# BatteryPower.net
KiCad netlist of a schematic drawn in Altium Designer
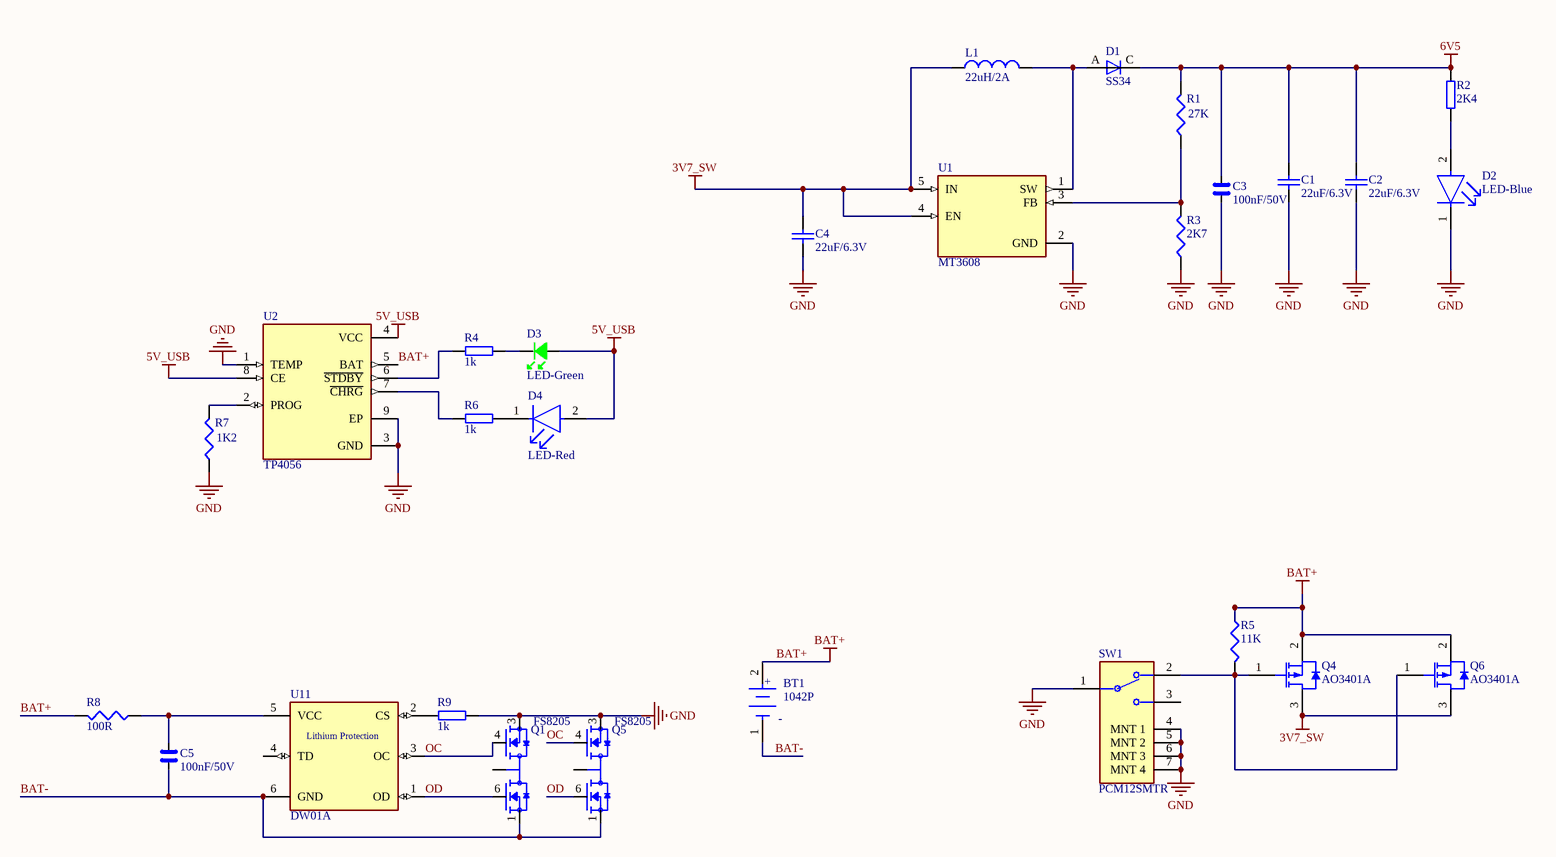
[diagram p0: BatteryPower.SchDoc]

(export (version "E")
  (design (tool "Eeschema 10.0.6"))
  (components
    (comp (ref "BT1")
      (value "1042P")
      (footprint "FP-1042P-MFG")
      (description "BATTERY HOLDER 18650 SMD TAB")
      (fields (field (name "LCSCPARTNO") "C2988620"))
      (libsource (lib "Altium Content Vault") (part "60d3b5b901a8747834971d0eb8cf3fd"))
    )
    (comp (ref "C1")
      (value "22uF/6.3V")
      (footprint "1608[0603]")
      (description "Capacitor")
      (fields (field (name "LCSCPARTNO") "C59461"))
      (libsource (lib "Miscellaneous Devices") (part "Cap"))
    )
    (comp (ref "C2")
      (value "22uF/6.3V")
      (footprint "1608[0603]")
      (description "Capacitor")
      (fields (field (name "LCSCPARTNO") "C59461"))
      (libsource (lib "Miscellaneous Devices") (part "Cap"))
    )
    (comp (ref "C3")
      (value "100nF/50V")
      (footprint "1608[0603]")
      (description "Cap Ceramic 0.1uF 50V X7R 20% SMD 0603 125C Paper T/R")
      (fields (field (name "LCSCPARTNO") "C14663"))
      (libsource (lib "Sch") (part "C"))
    )
    (comp (ref "C4")
      (value "22uF/6.3V")
      (footprint "1608[0603]")
      (description "Capacitor")
      (fields (field (name "LCSCPARTNO") "C59461"))
      (libsource (lib "Miscellaneous Devices") (part "Cap"))
    )
    (comp (ref "C5")
      (value "100nF/50V")
      (footprint "1608[0603]")
      (description "Cap Ceramic 0.1uF 50V X7R 20% SMD 0603 125C Paper T/R")
      (fields (field (name "LCSCPARTNO") "C14663"))
      (libsource (lib "Sch") (part "C"))
    )
    (comp (ref "D1")
      (value "SS34")
      (footprint "SMA:DIOM449X264X300L114X135N")
      (description "0.5mA@40V 40V Single 3A 0.55V@3A SMA(DO-214AC) Schottky")
      (fields (field (name "LCSCPARTNO") "C8678"))
      (libsource (lib "SMA") (part "EGF1B"))
    )
    (comp (ref "D2")
      (value "LED-Blue")
      (footprint "FP-LTST-C193TBKT-5A-MFG")
      (description "LED BLUE CLEAR CHIP SMD")
      (fields (field (name "LCSCPARTNO") "C72041"))
      (libsource (lib "Altium Content Vault") (part "8706943c75ba83719d021d2fdc84c58"))
    )
    (comp (ref "D3")
      (value "LED-Green")
      (footprint "LED0603G")
      (description "LED GREEN CLEAR CHIP SMD")
      (fields (field (name "LCSCPARTNO") "C72043"))
      (libsource (lib "Sch") (part "LED-G"))
    )
    (comp (ref "D4")
      (value "LED-Red")
      (footprint "FP-LTST-C193KRKT-5A-MFG")
      (description "LED RED CLEAR CHIP SMD")
      (fields (field (name "LCSCPARTNO") "C2286"))
      (libsource (lib "Altium Content Vault") (part "8706943c75ba83719d021d2fdc84c58"))
    )
    (comp (ref "L1")
      (value "22uH/2A")
      (footprint "INDM7166X18N")
      (description "Inductor")
      (fields (field (name "LCSCPARTNO") "C705336"))
      (libsource (lib "Miscellaneous Devices") (part "Inductor"))
    )
    (comp (ref "Q1")
      (value "FS8205")
      (footprint "SOT95P280X145-6N:SOT95P280X145-6N")
      (description "Dual N-Channel Enhancement Mode Power MOSFET")
      (fields (field (name "MF") "Fortune Semiconductor") (field (name "LCSCPARTNO") "C2830320"))
      (libsource (lib "FS8205") (part "FS8205"))
    )
    (comp (ref "Q4")
      (value "AO3401A")
      (footprint "AO-SOT-23-3L_V")
      (description "P-Channel MOSFET, 30 V, 4 A, -55 to 150 degC, 3-Pin SOT-23-3L, RoHS, Tape and Reel")
      (fields (field (name "LCSCPARTNO") "C15127"))
      (libsource (lib "Altium Content Vault") (part "PEMOS-GSD-3"))
    )
    (comp (ref "Q5")
      (value "FS8205")
      (footprint "SOT95P280X145-6N:SOT95P280X145-6N")
      (description "Dual N-Channel Enhancement Mode Power MOSFET")
      (fields (field (name "MF") "Fortune Semiconductor") (field (name "LCSCPARTNO") "C2830320"))
      (libsource (lib "FS8205") (part "FS8205"))
    )
    (comp (ref "Q6")
      (value "AO3401A")
      (footprint "AO-SOT-23-3L_V")
      (description "P-Channel MOSFET, 30 V, 4 A, -55 to 150 degC, 3-Pin SOT-23-3L, RoHS, Tape and Reel")
      (fields (field (name "LCSCPARTNO") "C15127"))
      (libsource (lib "Altium Content Vault") (part "PEMOS-GSD-3"))
    )
    (comp (ref "R1")
      (value "27K")
      (footprint "J1-0603")
      (description "Resistor")
      (fields (field (name "LCSCPARTNO") "C22967"))
      (libsource (lib "Miscellaneous Devices") (part "Res3"))
    )
    (comp (ref "R2")
      (value "2K4")
      (footprint "1608[0603]")
      (description "Res General Purpose Thick Film 0603 1% 1/10W ±100ppm/°C Molded SMD Paper T/R")
      (fields (field (name "LCSCPARTNO") "C22940"))
      (libsource (lib "Sch") (part "R"))
    )
    (comp (ref "R3")
      (value "2K7")
      (footprint "J1-0603")
      (description "Resistor")
      (fields (field (name "LCSCPARTNO") "C13167"))
      (libsource (lib "Miscellaneous Devices") (part "Res3"))
    )
    (comp (ref "R4")
      (value "1k")
      (footprint "1608[0603]")
      (description "Res General Purpose Thick Film 0603 1% 1/10W ±100ppm/°C Molded SMD Paper T/R")
      (fields (field (name "LCSCPARTNO") "C21190"))
      (libsource (lib "Sch") (part "R"))
    )
    (comp (ref "R5")
      (value "11K")
      (footprint "J1-0603")
      (description "Resistor")
      (fields (field (name "LCSCPARTNO") "C25950"))
      (libsource (lib "Miscellaneous Devices") (part "Res3"))
    )
    (comp (ref "R6")
      (value "1k")
      (footprint "1608[0603]")
      (description "Res General Purpose Thick Film 0603 1% 1/10W ±100ppm/°C Molded SMD Paper T/R")
      (fields (field (name "LCSCPARTNO") "C21190"))
      (libsource (lib "Sch") (part "R"))
    )
    (comp (ref "R7")
      (value "1K2")
      (footprint "J1-0603")
      (description "Resistor")
      (libsource (lib "Miscellaneous Devices") (part "Res3"))
    )
    (comp (ref "R8")
      (value "100R")
      (footprint "J1-0603")
      (description "Resistor")
      (libsource (lib "Miscellaneous Devices") (part "Res3"))
    )
    (comp (ref "R9")
      (value "1k")
      (footprint "1608[0603]")
      (description "Res General Purpose Thick Film 0603 1% 1/10W ±100ppm/°C Molded SMD Paper T/R")
      (fields (field (name "LCSCPARTNO") "C21190"))
      (libsource (lib "Sch") (part "R"))
    )
    (comp (ref "SW1")
      (value "PCM12SMTR")
      (footprint "FP-PCM12SMTR-MFG")
      (description "SWITCH SLIDE SPDT 300MA 6V")
      (fields (field (name "LCSCPARTNO") "C109335"))
      (libsource (lib "Altium Content Vault") (part "1a3f67d7e2b5469b171eeab59ffb4d2"))
    )
    (comp (ref "U1")
      (value "MT3608")
      (footprint "SOT95P280X145-6N:SOT95P280X145-6N")
      (description "High Efficiency 1.2MHz 2A Step Up Converter")
      (fields (field (name "LCSCPARTNO") "C84817"))
      (libsource (lib "MT3608") (part "MT3608"))
    )
    (comp (ref "U2")
      (value "TP4056")
      (footprint "SOP127P600X175-9N:SOP127P600X175-9N")
      (description "Complete single cell Li-Ion battery with a constant current / constant voltage linear charger")
      (fields (field (name "LCSCPARTNO") "C16581"))
      (libsource (lib "TP4056") (part "TP4056"))
    )
    (comp (ref "U11")
      (value "DW01A")
      (footprint "DW01A:SOT23-6")
      (description "SOT-23-6L Battery Management ICs ROHS")
      (fields (field (name "LCSCPARTNO") "C351410"))
      (libsource (lib "DW01A") (part "DW01A"))
    )
  )
  (nets
    (net (code "1") (name "/BAT-") (class "Default")
      (node (ref "BT1") (pin "1") (pinfunction "C_1") (pintype "passive"))
      (node (ref "C5") (pin "2") (pinfunction "2_2") (pintype "passive"))
      (node (ref "Q1") (pin "1") (pinfunction "S1_1") (pintype "passive"))
      (node (ref "Q5") (pin "1") (pinfunction "S1_1") (pintype "passive"))
      (node (ref "U11") (pin "6") (pinfunction "GND_6") (pintype "power_in"))
    )
    (net (code "2") (name "/OC") (class "Default")
      (node (ref "Q1") (pin "4") (pinfunction "G2_4") (pintype "passive"))
      (node (ref "Q5") (pin "4") (pinfunction "G2_4") (pintype "passive"))
      (node (ref "U11") (pin "3") (pinfunction "OC_3") (pintype "bidirectional"))
    )
    (net (code "3") (name "/OD") (class "Default")
      (node (ref "Q1") (pin "6") (pinfunction "G1_6") (pintype "passive"))
      (node (ref "Q5") (pin "6") (pinfunction "G1_6") (pintype "passive"))
      (node (ref "U11") (pin "1") (pinfunction "OD_1") (pintype "bidirectional"))
    )
    (net (code "4") (name "3V7_SW") (class "Default")
      (node (ref "C4") (pin "2") (pinfunction "2_2") (pintype "passive"))
      (node (ref "L1") (pin "1") (pinfunction "1_1") (pintype "passive"))
      (node (ref "Q4") (pin "3") (pinfunction "DRAIN_3") (pintype "passive"))
      (node (ref "Q6") (pin "3") (pinfunction "DRAIN_3") (pintype "passive"))
      (node (ref "U1") (pin "4") (pinfunction "EN_4") (pintype "input"))
      (node (ref "U1") (pin "5") (pinfunction "IN_5") (pintype "input"))
    )
    (net (code "5") (name "5V_USB") (class "Default")
      (node (ref "D3") (pin "1") (pinfunction "1_1") (pintype "passive"))
      (node (ref "D4") (pin "2") (pinfunction "A_2") (pintype "passive"))
      (node (ref "U2") (pin "4") (pinfunction "VCC_4") (pintype "power_in"))
      (node (ref "U2") (pin "8") (pinfunction "CE_8") (pintype "input"))
    )
    (net (code "6") (name "6V5") (class "Default")
      (node (ref "C1") (pin "2") (pinfunction "2_2") (pintype "passive"))
      (node (ref "C2") (pin "2") (pinfunction "2_2") (pintype "passive"))
      (node (ref "C3") (pin "1") (pinfunction "1_1") (pintype "passive"))
      (node (ref "D1") (pin "C") (pinfunction "C_C") (pintype "passive"))
      (node (ref "R1") (pin "2") (pinfunction "2_2") (pintype "passive"))
      (node (ref "R2") (pin "1") (pintype "passive"))
    )
    (net (code "7") (name "BAT+") (class "Default")
      (node (ref "BT1") (pin "2") (pinfunction "A_2") (pintype "passive"))
      (node (ref "Q4") (pin "2") (pinfunction "SOURCE_2") (pintype "passive"))
      (node (ref "Q6") (pin "2") (pinfunction "SOURCE_2") (pintype "passive"))
      (node (ref "R5") (pin "1") (pinfunction "1_1") (pintype "passive"))
      (node (ref "R8") (pin "2") (pinfunction "2_2") (pintype "passive"))
      (node (ref "U2") (pin "5") (pinfunction "BAT_5") (pintype "output"))
    )
    (net (code "8") (name "GND") (class "Default")
      (node (ref "C1") (pin "1") (pinfunction "1_1") (pintype "passive"))
      (node (ref "C2") (pin "1") (pinfunction "1_1") (pintype "passive"))
      (node (ref "C3") (pin "2") (pinfunction "2_2") (pintype "passive"))
      (node (ref "C4") (pin "1") (pinfunction "1_1") (pintype "passive"))
      (node (ref "D2") (pin "1") (pinfunction "C_1") (pintype "passive"))
      (node (ref "Q1") (pin "3") (pinfunction "S2_3") (pintype "passive"))
      (node (ref "Q5") (pin "3") (pinfunction "S2_3") (pintype "passive"))
      (node (ref "R3") (pin "1") (pinfunction "1_1") (pintype "passive"))
      (node (ref "R7") (pin "1") (pinfunction "1_1") (pintype "passive"))
      (node (ref "R9") (pin "1") (pintype "passive"))
      (node (ref "SW1") (pin "1") (pinfunction "1_1") (pintype "passive"))
      (node (ref "SW1") (pin "4") (pinfunction "MNT_1_4") (pintype "passive"))
      (node (ref "SW1") (pin "5") (pinfunction "MNT_2_5") (pintype "passive"))
      (node (ref "SW1") (pin "6") (pinfunction "MNT_3_6") (pintype "passive"))
      (node (ref "SW1") (pin "7") (pinfunction "MNT_4_7") (pintype "passive"))
      (node (ref "U1") (pin "2") (pinfunction "GND_2") (pintype "power_in"))
      (node (ref "U2") (pin "1") (pinfunction "TEMP_1") (pintype "input"))
      (node (ref "U2") (pin "3") (pinfunction "GND_3") (pintype "power_in"))
      (node (ref "U2") (pin "9") (pinfunction "EP_9") (pintype "passive"))
    )
    (net (code "9") (name "Net-(D2-A)") (class "Default")
      (node (ref "D2") (pin "2") (pinfunction "A_2") (pintype "passive"))
      (node (ref "R2") (pin "2") (pintype "passive"))
    )
    (net (code "10") (name "Net-(D3-Pad2)") (class "Default")
      (node (ref "D3") (pin "2") (pinfunction "2_2") (pintype "passive"))
      (node (ref "R4") (pin "2") (pintype "passive"))
    )
    (net (code "11") (name "Net-(D4-C)") (class "Default")
      (node (ref "D4") (pin "1") (pinfunction "C_1") (pintype "passive"))
      (node (ref "R6") (pin "2") (pintype "passive"))
    )
    (net (code "12") (name "Net-(Q1-D12-Pad2)") (class "Default")
      (node (ref "Q1") (pin "2") (pinfunction "D12_2") (pintype "passive"))
      (node (ref "Q1") (pin "5") (pinfunction "D12_5") (pintype "passive"))
    )
    (net (code "13") (name "Net-(Q4-GATE)") (class "Default")
      (node (ref "Q4") (pin "1") (pinfunction "GATE_1") (pintype "passive"))
      (node (ref "Q6") (pin "1") (pinfunction "GATE_1") (pintype "passive"))
      (node (ref "R5") (pin "2") (pinfunction "2_2") (pintype "passive"))
      (node (ref "SW1") (pin "2") (pinfunction "2_2") (pintype "passive"))
    )
    (net (code "14") (name "Net-(Q5-D12-Pad2)") (class "Default")
      (node (ref "Q5") (pin "2") (pinfunction "D12_2") (pintype "passive"))
      (node (ref "Q5") (pin "5") (pinfunction "D12_5") (pintype "passive"))
    )
    (net (code "15") (name "Net-(U1-FB)") (class "Default")
      (node (ref "R1") (pin "1") (pinfunction "1_1") (pintype "passive"))
      (node (ref "R3") (pin "2") (pinfunction "2_2") (pintype "passive"))
      (node (ref "U1") (pin "3") (pinfunction "FB_3") (pintype "input"))
    )
    (net (code "16") (name "Net-(U1-SW)") (class "Default")
      (node (ref "D1") (pin "A") (pinfunction "A_A") (pintype "passive"))
      (node (ref "L1") (pin "2") (pinfunction "2_2") (pintype "passive"))
      (node (ref "U1") (pin "1") (pinfunction "SW_1") (pintype "output"))
    )
    (net (code "17") (name "Net-(U2-PROG)") (class "Default")
      (node (ref "R7") (pin "2") (pinfunction "2_2") (pintype "passive"))
      (node (ref "U2") (pin "2") (pinfunction "PROG_2") (pintype "bidirectional"))
    )
    (net (code "18") (name "Net-(U2-~{CHRG})") (class "Default")
      (node (ref "R6") (pin "1") (pintype "passive"))
      (node (ref "U2") (pin "7") (pinfunction "~{CHRG}_7") (pintype "output"))
    )
    (net (code "19") (name "Net-(U2-~{STDBY})") (class "Default")
      (node (ref "R4") (pin "1") (pintype "passive"))
      (node (ref "U2") (pin "6") (pinfunction "~{STDBY}_6") (pintype "output"))
    )
    (net (code "20") (name "Net-(U11-CS)") (class "Default")
      (node (ref "R9") (pin "2") (pintype "passive"))
      (node (ref "U11") (pin "2") (pinfunction "CS_2") (pintype "bidirectional"))
    )
    (net (code "21") (name "Net-(U11-VCC)") (class "Default")
      (node (ref "C5") (pin "1") (pinfunction "1_1") (pintype "passive"))
      (node (ref "R8") (pin "1") (pinfunction "1_1") (pintype "passive"))
      (node (ref "U11") (pin "5") (pinfunction "VCC_5") (pintype "power_in"))
    )
    (net (code "22") (name "unconnected-(SW1-Pad3)") (class "Default")
      (node (ref "SW1") (pin "3") (pinfunction "3_3") (pintype "passive"))
    )
    (net (code "23") (name "unconnected-(U11-TD-Pad4)") (class "Default")
      (node (ref "U11") (pin "4") (pinfunction "TD_4") (pintype "bidirectional"))
    )
  )
)
